# Voltage_BypassCapacitors.net
KiCad netlist of a schematic drawn in Altium Designer
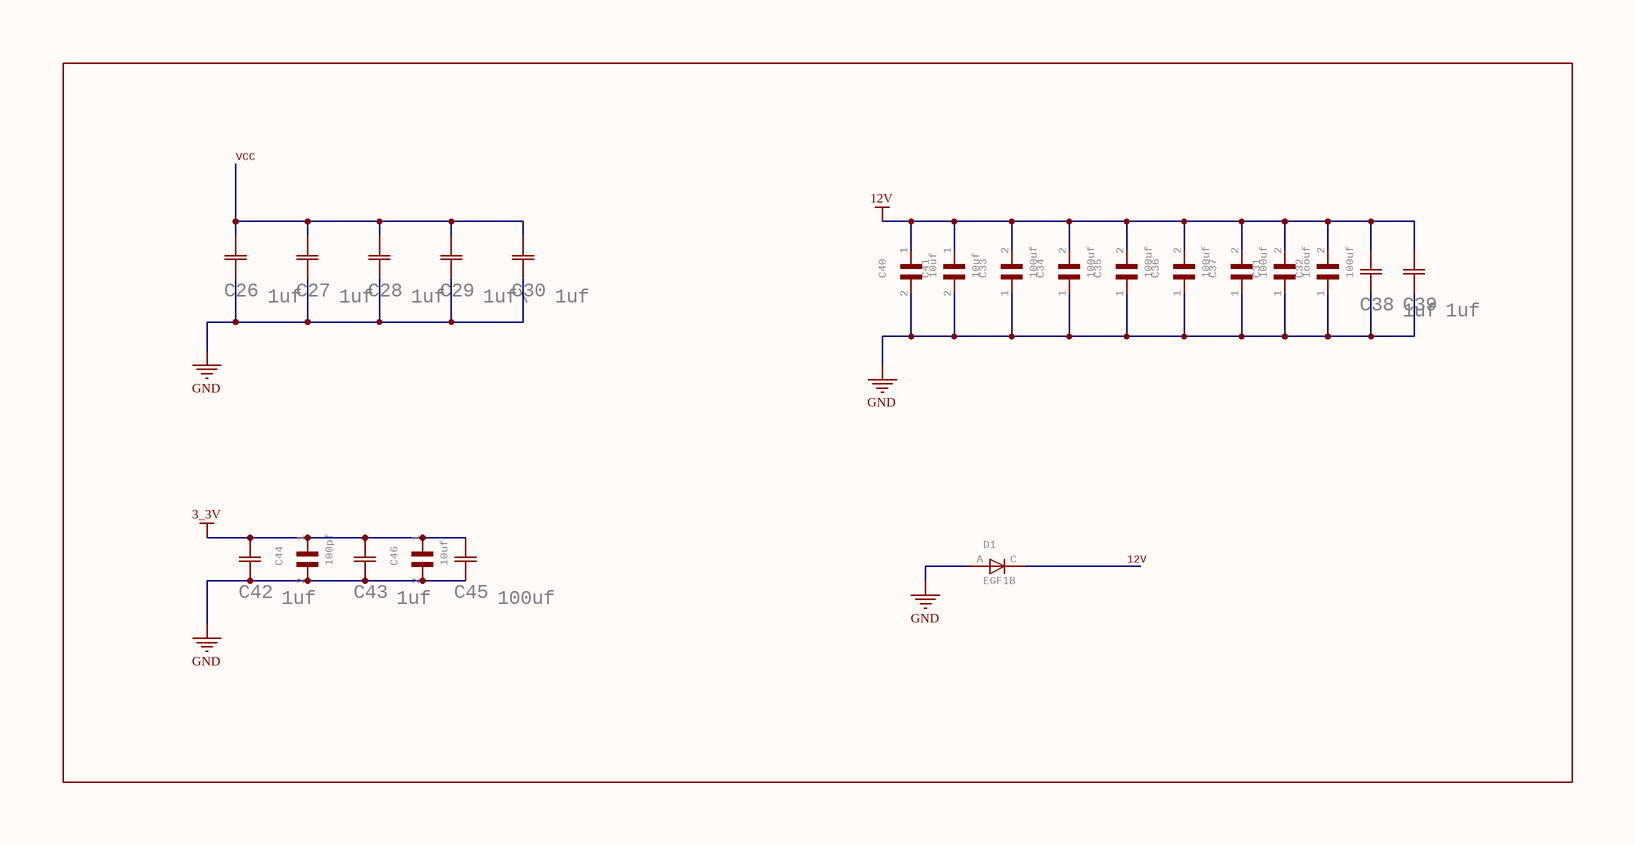
[diagram p0: Voltage_BypassCapacitors.SchDoc]

(export (version "E")
  (design (tool "Eeschema 10.0.6"))
  (components
    (comp (ref "C26")
      (value "1uf")
      (footprint "YAG_CC0603_YAG")
      (fields (field (name "MANUFACTURER_PART_NUMBER") "CC0603KRX7R7BB105"))
      (libsource (lib "Cap 1uf") (part "CC0603KRX7R7BB105"))
    )
    (comp (ref "C27")
      (value "1uf")
      (footprint "YAG_CC0603_YAG")
      (fields (field (name "MANUFACTURER_PART_NUMBER") "CC0603KRX7R7BB105"))
      (libsource (lib "Cap 1uf") (part "CC0603KRX7R7BB105"))
    )
    (comp (ref "C28")
      (value "1uf")
      (footprint "YAG_CC0603_YAG")
      (fields (field (name "MANUFACTURER_PART_NUMBER") "CC0603KRX7R7BB105"))
      (libsource (lib "Cap 1uf") (part "CC0603KRX7R7BB105"))
    )
    (comp (ref "C29")
      (value "1u~{f}")
      (footprint "YAG_CC0603_YAG")
      (fields (field (name "MANUFACTURER_PART_NUMBER") "CC0603KRX7R7BB105"))
      (libsource (lib "Cap 1uf") (part "CC0603KRX7R7BB105"))
    )
    (comp (ref "C30")
      (value "1uf")
      (footprint "YAG_CC0603_YAG")
      (fields (field (name "MANUFACTURER_PART_NUMBER") "CC0603KRX7R7BB105"))
      (libsource (lib "Cap 1uf") (part "CC0603KRX7R7BB105"))
    )
    (comp (ref "C31")
      (value "1oouf")
      (footprint "CAPC3225X280N")
      (fields
        (field (name "DIGI-KEY_PART_NUMBER") "DIGI-KEY_PART_NUMBER")
        (field (name "MF") "KEMET")
        (field (name "MP") "C1210C107M4PAC7800")
      )
      (libsource (lib "Cap 100uf 16v") (part "C1210C107M4PAC7800"))
    )
    (comp (ref "C32")
      (value "100uf")
      (footprint "CAPC3225X280N")
      (fields
        (field (name "DIGI-KEY_PART_NUMBER") "DIGI-KEY_PART_NUMBER")
        (field (name "MF") "KEMET")
        (field (name "MP") "C1210C107M4PAC7800")
      )
      (libsource (lib "Cap 100uf 16v") (part "C1210C107M4PAC7800"))
    )
    (comp (ref "C33")
      (value "100uf")
      (footprint "CAPC3225X280N")
      (fields
        (field (name "DIGI-KEY_PART_NUMBER") "DIGI-KEY_PART_NUMBER")
        (field (name "MF") "KEMET")
        (field (name "MP") "C1210C107M4PAC7800")
      )
      (libsource (lib "Cap 100uf 16v") (part "C1210C107M4PAC7800"))
    )
    (comp (ref "C34")
      (value "100uf")
      (footprint "CAPC3225X280N")
      (fields
        (field (name "DIGI-KEY_PART_NUMBER") "DIGI-KEY_PART_NUMBER")
        (field (name "MF") "KEMET")
        (field (name "MP") "C1210C107M4PAC7800")
      )
      (libsource (lib "Cap 100uf 16v") (part "C1210C107M4PAC7800"))
    )
    (comp (ref "C35")
      (value "100uf")
      (footprint "CAPC3225X280N")
      (fields
        (field (name "DIGI-KEY_PART_NUMBER") "DIGI-KEY_PART_NUMBER")
        (field (name "MF") "KEMET")
        (field (name "MP") "C1210C107M4PAC7800")
      )
      (libsource (lib "Cap 100uf 16v") (part "C1210C107M4PAC7800"))
    )
    (comp (ref "C36")
      (value "100uf")
      (footprint "CAPC3225X280N")
      (fields
        (field (name "DIGI-KEY_PART_NUMBER") "DIGI-KEY_PART_NUMBER")
        (field (name "MF") "KEMET")
        (field (name "MP") "C1210C107M4PAC7800")
      )
      (libsource (lib "Cap 100uf 16v") (part "C1210C107M4PAC7800"))
    )
    (comp (ref "C37")
      (value "100uf")
      (footprint "CAPC3225X280N")
      (fields
        (field (name "DIGI-KEY_PART_NUMBER") "DIGI-KEY_PART_NUMBER")
        (field (name "MF") "KEMET")
        (field (name "MP") "C1210C107M4PAC7800")
      )
      (libsource (lib "Cap 100uf 16v") (part "C1210C107M4PAC7800"))
    )
    (comp (ref "C38")
      (value "1uf")
      (footprint "YAG_CC0603_YAG")
      (fields (field (name "MANUFACTURER_PART_NUMBER") "CC0603KRX7R7BB105"))
      (libsource (lib "Cap 1uf") (part "CC0603KRX7R7BB105"))
    )
    (comp (ref "C39")
      (value "1uf")
      (footprint "YAG_CC0603_YAG")
      (fields (field (name "MANUFACTURER_PART_NUMBER") "CC0603KRX7R7BB105"))
      (libsource (lib "Cap 1uf") (part "CC0603KRX7R7BB105"))
    )
    (comp (ref "C40")
      (value "10uf")
      (footprint "CAPC2012X70")
      (description "KC 10ÂµF 0805 10% 16V X5R")
      (fields (field (name "DIGI-KEY_PART_NUMBER") "311-1865-1-ND") (field (name "MF") "Yageo"))
      (libsource (lib "Cap 10uf") (part "CC0805KKX5R7BB106"))
    )
    (comp (ref "C41")
      (value "10uf")
      (footprint "CAPC2012X70")
      (description "KC 10ÂµF 0805 10% 16V X5R")
      (fields (field (name "DIGI-KEY_PART_NUMBER") "311-1865-1-ND") (field (name "MF") "Yageo"))
      (libsource (lib "Cap 10uf") (part "CC0805KKX5R7BB106"))
    )
    (comp (ref "C42")
      (value "1uf")
      (footprint "YAG_CC0603_YAG")
      (fields (field (name "MANUFACTURER_PART_NUMBER") "CC0603KRX7R7BB105"))
      (libsource (lib "Cap 1uf") (part "CC0603KRX7R7BB105"))
    )
    (comp (ref "C43")
      (value "1uf")
      (footprint "YAG_CC0603_YAG")
      (fields (field (name "MANUFACTURER_PART_NUMBER") "CC0603KRX7R7BB105"))
      (libsource (lib "Cap 1uf") (part "CC0603KRX7R7BB105"))
    )
    (comp (ref "C44")
      (value "100pf")
      (footprint "CAPC1608X90")
      (description "CAP CER 100PF 16V X7R 0603")
      (fields (field (name "DIGI-KEY_PART_NUMBER") "311-4062-1-ND") (field (name "MF") "Yageo"))
      (libsource (lib "Cap 100p") (part "CC0603KRX7R7BB101"))
    )
    (comp (ref "C45")
      (value "100uf")
      (footprint "CAP_CC1210_YAG")
      (fields
        (field (name "MANUFACTURER_PART_NUMBER") "CC1210MKX5R5BB107")
        (field (name "COPYRIGHT") "Copyright (C) 2018 Accelerated Designs. All rights reserved")
      )
      (libsource (lib "Cap 100uf 6.3v") (part "CC1210MKX5R5BB107"))
    )
    (comp (ref "C46")
      (value "10uf")
      (footprint "CAPC2012X70")
      (description "KC 10ÂµF 0805 10% 16V X5R")
      (fields (field (name "DIGI-KEY_PART_NUMBER") "311-1865-1-ND") (field (name "MF") "Yageo"))
      (libsource (lib "Cap 10uf") (part "CC0805KKX5R7BB106"))
    )
    (comp (ref "D1")
      (value "EGF1B")
      (footprint "DIOM449X264X300L114X135N")
      (description "EGF1B Series 1 A 100 V 50 ns Surface Mount Fast Recovery Rectifier - DO-214AC Check prices")
      (fields
        (field (name "MF") "ON Semiconductor")
        (field (name "LIBRARYNAME") "AC214 zenzer diode replace")
      )
      (libsource (lib "AC214 zenzer diode replace") (part "EGF1B"))
    )
  )
  (nets
    (net (code "1") (name "/VCC") (class "Default")
      (node (ref "C26") (pin "2") (pinfunction "2_2") (pintype "passive"))
      (node (ref "C27") (pin "2") (pinfunction "2_2") (pintype "passive"))
      (node (ref "C28") (pin "2") (pinfunction "2_2") (pintype "passive"))
      (node (ref "C29") (pin "2") (pinfunction "2_2") (pintype "passive"))
      (node (ref "C30") (pin "2") (pinfunction "2_2") (pintype "passive"))
    )
    (net (code "2") (name "3_3V") (class "Default")
      (node (ref "C42") (pin "2") (pinfunction "2_2") (pintype "passive"))
      (node (ref "C43") (pin "2") (pinfunction "2_2") (pintype "passive"))
      (node (ref "C44") (pin "1") (pinfunction "1_1") (pintype "passive"))
      (node (ref "C45") (pin "2") (pinfunction "2_2") (pintype "passive"))
      (node (ref "C46") (pin "1") (pinfunction "1_1") (pintype "passive"))
    )
    (net (code "3") (name "12V") (class "Default")
      (node (ref "C31") (pin "2") (pinfunction "2_2") (pintype "passive"))
      (node (ref "C32") (pin "2") (pinfunction "2_2") (pintype "passive"))
      (node (ref "C33") (pin "2") (pinfunction "2_2") (pintype "passive"))
      (node (ref "C34") (pin "2") (pinfunction "2_2") (pintype "passive"))
      (node (ref "C35") (pin "2") (pinfunction "2_2") (pintype "passive"))
      (node (ref "C36") (pin "2") (pinfunction "2_2") (pintype "passive"))
      (node (ref "C37") (pin "2") (pinfunction "2_2") (pintype "passive"))
      (node (ref "C38") (pin "2") (pinfunction "2_2") (pintype "passive"))
      (node (ref "C39") (pin "2") (pinfunction "2_2") (pintype "passive"))
      (node (ref "C40") (pin "1") (pinfunction "1_1") (pintype "passive"))
      (node (ref "C41") (pin "1") (pinfunction "1_1") (pintype "passive"))
      (node (ref "D1") (pin "C") (pinfunction "C_C") (pintype "passive"))
    )
    (net (code "4") (name "GND") (class "Default")
      (node (ref "C26") (pin "1") (pinfunction "1_1") (pintype "passive"))
      (node (ref "C27") (pin "1") (pinfunction "1_1") (pintype "passive"))
      (node (ref "C28") (pin "1") (pinfunction "1_1") (pintype "passive"))
      (node (ref "C29") (pin "1") (pinfunction "1_1") (pintype "passive"))
      (node (ref "C30") (pin "1") (pinfunction "1_1") (pintype "passive"))
      (node (ref "C31") (pin "1") (pinfunction "1_1") (pintype "passive"))
      (node (ref "C32") (pin "1") (pinfunction "1_1") (pintype "passive"))
      (node (ref "C33") (pin "1") (pinfunction "1_1") (pintype "passive"))
      (node (ref "C34") (pin "1") (pinfunction "1_1") (pintype "passive"))
      (node (ref "C35") (pin "1") (pinfunction "1_1") (pintype "passive"))
      (node (ref "C36") (pin "1") (pinfunction "1_1") (pintype "passive"))
      (node (ref "C37") (pin "1") (pinfunction "1_1") (pintype "passive"))
      (node (ref "C38") (pin "1") (pinfunction "1_1") (pintype "passive"))
      (node (ref "C39") (pin "1") (pinfunction "1_1") (pintype "passive"))
      (node (ref "C40") (pin "2") (pinfunction "2_2") (pintype "passive"))
      (node (ref "C41") (pin "2") (pinfunction "2_2") (pintype "passive"))
      (node (ref "C42") (pin "1") (pinfunction "1_1") (pintype "passive"))
      (node (ref "C43") (pin "1") (pinfunction "1_1") (pintype "passive"))
      (node (ref "C44") (pin "2") (pinfunction "2_2") (pintype "passive"))
      (node (ref "C45") (pin "1") (pinfunction "1_1") (pintype "passive"))
      (node (ref "C46") (pin "2") (pinfunction "2_2") (pintype "passive"))
      (node (ref "D1") (pin "A") (pinfunction "A_A") (pintype "passive"))
    )
  )
)
